# Mid485.net
KiCad netlist of a schematic drawn in Altium Designer
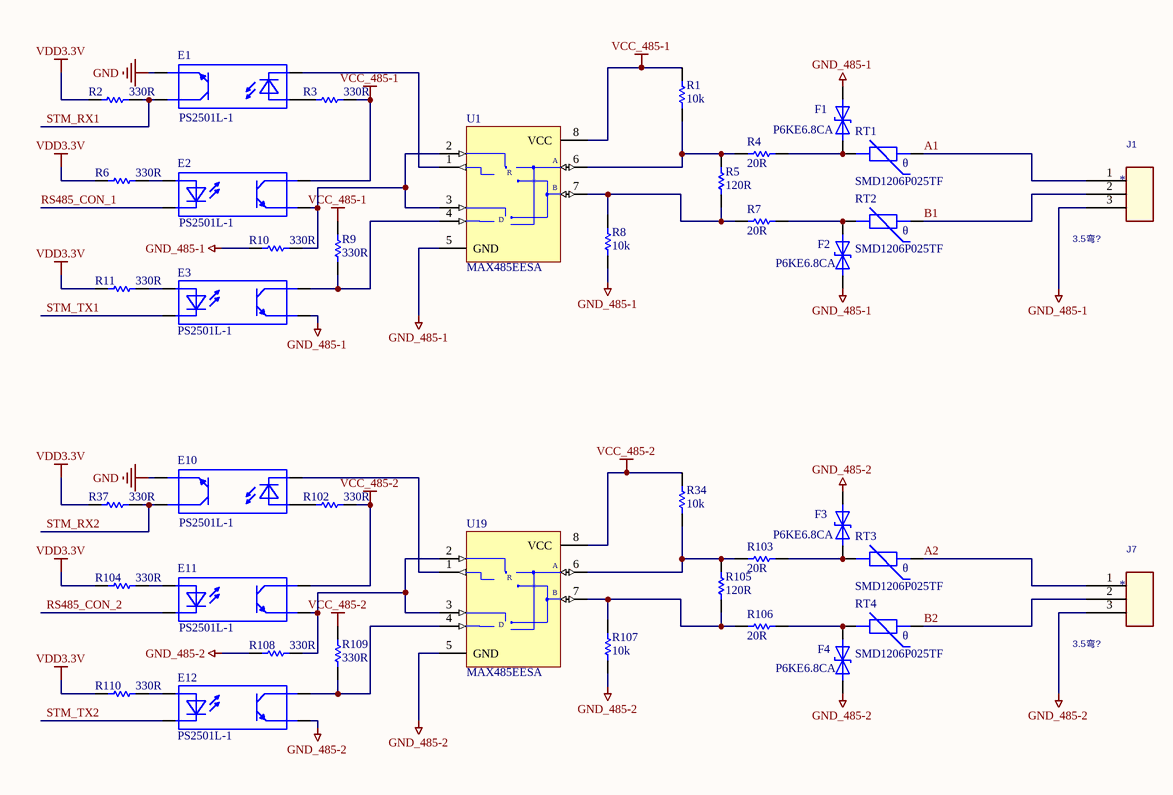
[diagram p0: Mid485.SchDoc]

(export (version "E")
  (design (tool "Eeschema 10.0.6"))
  (components
    (comp (ref "E1")
      (value "PS2501L-1")
      (footprint "NEC2501")
      (description "光耦")
      (libsource (lib "*") (part "OPTO1"))
    )
    (comp (ref "E2")
      (value "PS2501L-1")
      (footprint "NEC2501")
      (description "光耦")
      (libsource (lib "*") (part "OPTO1"))
    )
    (comp (ref "E3")
      (value "PS2501L-1")
      (footprint "NEC2501")
      (description "光耦")
      (libsource (lib "*") (part "OPTO1"))
    )
    (comp (ref "E10")
      (value "PS2501L-1")
      (footprint "NEC2501")
      (description "光耦")
      (libsource (lib "*") (part "OPTO1"))
    )
    (comp (ref "E11")
      (value "PS2501L-1")
      (footprint "NEC2501")
      (description "光耦")
      (libsource (lib "*") (part "OPTO1"))
    )
    (comp (ref "E12")
      (value "PS2501L-1")
      (footprint "NEC2501")
      (description "光耦")
      (libsource (lib "*") (part "OPTO1"))
    )
    (comp (ref "F1")
      (value "P6KE6.8CA")
      (footprint "P6KE6,8CA")
      (description "快速瞬变二极管")
      (libsource (lib "*") (part "TVS"))
    )
    (comp (ref "F2")
      (value "P6KE6.8CA")
      (footprint "P6KE6,8CA")
      (description "快速瞬变二极管")
      (libsource (lib "*") (part "TVS"))
    )
    (comp (ref "F3")
      (value "P6KE6.8CA")
      (footprint "P6KE6,8CA")
      (description "快速瞬变二极管")
      (libsource (lib "*") (part "TVS"))
    )
    (comp (ref "F4")
      (value "P6KE6.8CA")
      (footprint "P6KE6,8CA")
      (description "快速瞬变二极管")
      (libsource (lib "*") (part "TVS"))
    )
    (comp (ref "J1")
      (value "*")
      (footprint "3.5-P3")
      (fields (field (name "ALTIUM_UNNAMED_1") "3.5弯?"))
      (libsource (lib "*") (part "CON3"))
    )
    (comp (ref "J7")
      (value "*")
      (footprint "3.5-P3")
      (fields (field (name "ALTIUM_UNNAMED_1") "3.5弯?"))
      (libsource (lib "*") (part "CON3"))
    )
    (comp (ref "R1")
      (value "10k")
      (footprint "0805")
      (description "Semiconductor Resistor")
      (fields (field (name "Comment") "Res Semi") (field (name "PUBLISHER") "Altium Limited"))
      (libsource (lib "Miscellaneous Devices") (part "Res Semi"))
    )
    (comp (ref "R2")
      (value "330R")
      (footprint "0805")
      (description "Semiconductor Resistor")
      (fields (field (name "Comment") "Res Semi") (field (name "PUBLISHER") "Altium Limited"))
      (libsource (lib "Miscellaneous Devices") (part "Res Semi"))
    )
    (comp (ref "R3")
      (value "330R")
      (footprint "0805")
      (description "Semiconductor Resistor")
      (fields (field (name "Comment") "Res Semi") (field (name "PUBLISHER") "Altium Limited"))
      (libsource (lib "Miscellaneous Devices") (part "Res Semi"))
    )
    (comp (ref "R4")
      (value "20R")
      (footprint "0805")
      (description "Semiconductor Resistor")
      (fields (field (name "Comment") "Res Semi") (field (name "PUBLISHER") "Altium Limited"))
      (libsource (lib "Miscellaneous Devices") (part "Res Semi"))
    )
    (comp (ref "R5")
      (value "120R")
      (footprint "0805")
      (description "Semiconductor Resistor")
      (fields (field (name "Comment") "Res Semi") (field (name "PUBLISHER") "Altium Limited"))
      (libsource (lib "Miscellaneous Devices") (part "Res Semi"))
    )
    (comp (ref "R6")
      (value "330R")
      (footprint "0805")
      (description "Semiconductor Resistor")
      (fields (field (name "Comment") "Res Semi") (field (name "PUBLISHER") "Altium Limited"))
      (libsource (lib "Miscellaneous Devices") (part "Res Semi"))
    )
    (comp (ref "R7")
      (value "20R")
      (footprint "0805")
      (description "Semiconductor Resistor")
      (fields (field (name "Comment") "Res Semi") (field (name "PUBLISHER") "Altium Limited"))
      (libsource (lib "Miscellaneous Devices") (part "Res Semi"))
    )
    (comp (ref "R8")
      (value "10k")
      (footprint "0805")
      (description "Semiconductor Resistor")
      (fields (field (name "Comment") "Res Semi") (field (name "PUBLISHER") "Altium Limited"))
      (libsource (lib "Miscellaneous Devices") (part "Res Semi"))
    )
    (comp (ref "R9")
      (value "330R")
      (footprint "0805")
      (description "Semiconductor Resistor")
      (fields (field (name "Comment") "Res Semi") (field (name "PUBLISHER") "Altium Limited"))
      (libsource (lib "Miscellaneous Devices") (part "Res Semi"))
    )
    (comp (ref "R10")
      (value "330R")
      (footprint "0805")
      (description "Semiconductor Resistor")
      (fields (field (name "Comment") "Res Semi") (field (name "PUBLISHER") "Altium Limited"))
      (libsource (lib "Miscellaneous Devices") (part "Res Semi"))
    )
    (comp (ref "R11")
      (value "330R")
      (footprint "0805")
      (description "Semiconductor Resistor")
      (fields (field (name "Comment") "Res Semi") (field (name "PUBLISHER") "Altium Limited"))
      (libsource (lib "Miscellaneous Devices") (part "Res Semi"))
    )
    (comp (ref "R34")
      (value "10k")
      (footprint "0805")
      (description "Semiconductor Resistor")
      (fields (field (name "Comment") "Res Semi") (field (name "PUBLISHER") "Altium Limited"))
      (libsource (lib "Miscellaneous Devices") (part "Res Semi"))
    )
    (comp (ref "R37")
      (value "330R")
      (footprint "0805")
      (description "Semiconductor Resistor")
      (fields (field (name "Comment") "Res Semi") (field (name "PUBLISHER") "Altium Limited"))
      (libsource (lib "Miscellaneous Devices") (part "Res Semi"))
    )
    (comp (ref "R102")
      (value "330R")
      (footprint "0805")
      (description "Semiconductor Resistor")
      (fields (field (name "Comment") "Res Semi") (field (name "PUBLISHER") "Altium Limited"))
      (libsource (lib "Miscellaneous Devices") (part "Res Semi"))
    )
    (comp (ref "R103")
      (value "20R")
      (footprint "0805")
      (description "Semiconductor Resistor")
      (fields (field (name "Comment") "Res Semi") (field (name "PUBLISHER") "Altium Limited"))
      (libsource (lib "Miscellaneous Devices") (part "Res Semi"))
    )
    (comp (ref "R104")
      (value "330R")
      (footprint "0805")
      (description "Semiconductor Resistor")
      (fields (field (name "Comment") "Res Semi") (field (name "PUBLISHER") "Altium Limited"))
      (libsource (lib "Miscellaneous Devices") (part "Res Semi"))
    )
    (comp (ref "R105")
      (value "120R")
      (footprint "0805")
      (description "Semiconductor Resistor")
      (fields (field (name "Comment") "Res Semi") (field (name "PUBLISHER") "Altium Limited"))
      (libsource (lib "Miscellaneous Devices") (part "Res Semi"))
    )
    (comp (ref "R106")
      (value "20R")
      (footprint "0805")
      (description "Semiconductor Resistor")
      (fields (field (name "Comment") "Res Semi") (field (name "PUBLISHER") "Altium Limited"))
      (libsource (lib "Miscellaneous Devices") (part "Res Semi"))
    )
    (comp (ref "R107")
      (value "10k")
      (footprint "0805")
      (description "Semiconductor Resistor")
      (fields (field (name "Comment") "Res Semi") (field (name "PUBLISHER") "Altium Limited"))
      (libsource (lib "Miscellaneous Devices") (part "Res Semi"))
    )
    (comp (ref "R108")
      (value "330R")
      (footprint "0805")
      (description "Semiconductor Resistor")
      (fields (field (name "Comment") "Res Semi") (field (name "PUBLISHER") "Altium Limited"))
      (libsource (lib "Miscellaneous Devices") (part "Res Semi"))
    )
    (comp (ref "R109")
      (value "330R")
      (footprint "0805")
      (description "Semiconductor Resistor")
      (fields (field (name "Comment") "Res Semi") (field (name "PUBLISHER") "Altium Limited"))
      (libsource (lib "Miscellaneous Devices") (part "Res Semi"))
    )
    (comp (ref "R110")
      (value "330R")
      (footprint "0805")
      (description "Semiconductor Resistor")
      (fields (field (name "Comment") "Res Semi") (field (name "PUBLISHER") "Altium Limited"))
      (libsource (lib "Miscellaneous Devices") (part "Res Semi"))
    )
    (comp (ref "RT1")
      (value "SMD1206P025TF")
      (footprint "1206")
      (description "热敏电阻")
      (libsource (lib "*") (part "PTC"))
    )
    (comp (ref "RT2")
      (value "SMD1206P025TF")
      (footprint "1206")
      (description "热敏电阻")
      (libsource (lib "*") (part "PTC"))
    )
    (comp (ref "RT3")
      (value "SMD1206P025TF")
      (footprint "1206")
      (description "热敏电阻")
      (libsource (lib "*") (part "PTC"))
    )
    (comp (ref "RT4")
      (value "SMD1206P025TF")
      (footprint "1206")
      (description "热敏电阻")
      (libsource (lib "*") (part "PTC"))
    )
    (comp (ref "U1")
      (value "MAX485EESA")
      (footprint "NSO8")
      (description "Low-Power, Slew-Rate-Limited RS-485/RS-422 Transceiver")
      (fields (field (name "PUBLISHER") "Altium Limited"))
      (libsource (lib "main board") (part "MAX485ESA"))
    )
    (comp (ref "U19")
      (value "MAX485EESA")
      (footprint "NSO8")
      (description "Low-Power, Slew-Rate-Limited RS-485/RS-422 Transceiver")
      (fields (field (name "PUBLISHER") "Altium Limited"))
      (libsource (lib "main board") (part "MAX485ESA"))
    )
  )
  (nets
    (net (code "1") (name "/A1") (class "Default")
      (node (ref "J1") (pin "1") (pinfunction "1_1") (pintype "passive"))
      (node (ref "RT1") (pin "2") (pintype "passive"))
    )
    (net (code "2") (name "/A2") (class "Default")
      (node (ref "J7") (pin "1") (pinfunction "1_1") (pintype "passive"))
      (node (ref "RT3") (pin "2") (pintype "passive"))
    )
    (net (code "3") (name "/B1") (class "Default")
      (node (ref "J1") (pin "2") (pinfunction "2_2") (pintype "passive"))
      (node (ref "RT2") (pin "2") (pintype "passive"))
    )
    (net (code "4") (name "/B2") (class "Default")
      (node (ref "J7") (pin "2") (pinfunction "2_2") (pintype "passive"))
      (node (ref "RT4") (pin "2") (pintype "passive"))
    )
    (net (code "5") (name "/RS485_CON_1") (class "Default") (node (ref "E2") (pin "2") (pintype "passive")))
    (net (code "6") (name "/RS485_CON_2") (class "Default") (node (ref "E11") (pin "2") (pintype "passive")))
    (net (code "7") (name "/STM_RX1") (class "Default")
      (node (ref "E1") (pin "4") (pintype "passive"))
      (node (ref "R2") (pin "1") (pinfunction "1_1") (pintype "passive"))
    )
    (net (code "8") (name "/STM_RX2") (class "Default")
      (node (ref "E10") (pin "4") (pintype "passive"))
      (node (ref "R37") (pin "1") (pinfunction "1_1") (pintype "passive"))
    )
    (net (code "9") (name "/STM_TX1") (class "Default") (node (ref "E3") (pin "2") (pintype "passive")))
    (net (code "10") (name "/STM_TX2") (class "Default") (node (ref "E12") (pin "2") (pintype "passive")))
    (net (code "11") (name "GND") (class "Default")
      (node (ref "E1") (pin "3") (pintype "passive"))
      (node (ref "E10") (pin "3") (pintype "passive"))
    )
    (net (code "12") (name "GND_485-1") (class "Default")
      (node (ref "E3") (pin "3") (pintype "passive"))
      (node (ref "F1") (pin "1") (pintype "passive"))
      (node (ref "F2") (pin "2") (pintype "passive"))
      (node (ref "J1") (pin "3") (pinfunction "3_3") (pintype "passive"))
      (node (ref "R10") (pin "2") (pinfunction "2_2") (pintype "passive"))
      (node (ref "R8") (pin "2") (pinfunction "2_2") (pintype "passive"))
      (node (ref "U1") (pin "5") (pinfunction "GND_5") (pintype "power_in"))
    )
    (net (code "13") (name "GND_485-2") (class "Default")
      (node (ref "E12") (pin "3") (pintype "passive"))
      (node (ref "F3") (pin "1") (pintype "passive"))
      (node (ref "F4") (pin "2") (pintype "passive"))
      (node (ref "J7") (pin "3") (pinfunction "3_3") (pintype "passive"))
      (node (ref "R107") (pin "2") (pinfunction "2_2") (pintype "passive"))
      (node (ref "R108") (pin "2") (pinfunction "2_2") (pintype "passive"))
      (node (ref "U19") (pin "5") (pinfunction "GND_5") (pintype "power_in"))
    )
    (net (code "14") (name "Net-(E1-Pad1)") (class "Default")
      (node (ref "E1") (pin "1") (pintype "passive"))
      (node (ref "R3") (pin "2") (pinfunction "2_2") (pintype "passive"))
    )
    (net (code "15") (name "Net-(E2-Pad1)") (class "Default")
      (node (ref "E2") (pin "1") (pintype "passive"))
      (node (ref "R6") (pin "1") (pinfunction "1_1") (pintype "passive"))
    )
    (net (code "16") (name "Net-(E3-Pad1)") (class "Default")
      (node (ref "E3") (pin "1") (pintype "passive"))
      (node (ref "R11") (pin "1") (pinfunction "1_1") (pintype "passive"))
    )
    (net (code "17") (name "Net-(E10-Pad1)") (class "Default")
      (node (ref "E10") (pin "1") (pintype "passive"))
      (node (ref "R102") (pin "2") (pinfunction "2_2") (pintype "passive"))
    )
    (net (code "18") (name "Net-(E11-Pad1)") (class "Default")
      (node (ref "E11") (pin "1") (pintype "passive"))
      (node (ref "R104") (pin "1") (pinfunction "1_1") (pintype "passive"))
    )
    (net (code "19") (name "Net-(E12-Pad1)") (class "Default")
      (node (ref "E12") (pin "1") (pintype "passive"))
      (node (ref "R110") (pin "1") (pinfunction "1_1") (pintype "passive"))
    )
    (net (code "20") (name "Net-(F1-Pad2)") (class "Default")
      (node (ref "F1") (pin "2") (pintype "passive"))
      (node (ref "R4") (pin "2") (pinfunction "2_2") (pintype "passive"))
      (node (ref "RT1") (pin "1") (pintype "passive"))
    )
    (net (code "21") (name "Net-(F2-Pad1)") (class "Default")
      (node (ref "F2") (pin "1") (pintype "passive"))
      (node (ref "R7") (pin "2") (pinfunction "2_2") (pintype "passive"))
      (node (ref "RT2") (pin "1") (pintype "passive"))
    )
    (net (code "22") (name "Net-(F3-Pad2)") (class "Default")
      (node (ref "F3") (pin "2") (pintype "passive"))
      (node (ref "R103") (pin "2") (pinfunction "2_2") (pintype "passive"))
      (node (ref "RT3") (pin "1") (pintype "passive"))
    )
    (net (code "23") (name "Net-(F4-Pad1)") (class "Default")
      (node (ref "F4") (pin "1") (pintype "passive"))
      (node (ref "R106") (pin "2") (pinfunction "2_2") (pintype "passive"))
      (node (ref "RT4") (pin "1") (pintype "passive"))
    )
    (net (code "24") (name "Net-(U1-A)") (class "Default")
      (node (ref "R1") (pin "2") (pinfunction "2_2") (pintype "passive"))
      (node (ref "R4") (pin "1") (pinfunction "1_1") (pintype "passive"))
      (node (ref "R5") (pin "1") (pinfunction "1_1") (pintype "passive"))
      (node (ref "U1") (pin "6") (pinfunction "A_6") (pintype "bidirectional"))
    )
    (net (code "25") (name "Net-(U1-B)") (class "Default")
      (node (ref "R5") (pin "2") (pinfunction "2_2") (pintype "passive"))
      (node (ref "R7") (pin "1") (pinfunction "1_1") (pintype "passive"))
      (node (ref "R8") (pin "1") (pinfunction "1_1") (pintype "passive"))
      (node (ref "U1") (pin "7") (pinfunction "B_7") (pintype "bidirectional"))
    )
    (net (code "26") (name "Net-(U1-DE)") (class "Default")
      (node (ref "E2") (pin "3") (pintype "passive"))
      (node (ref "R10") (pin "1") (pinfunction "1_1") (pintype "passive"))
      (node (ref "U1") (pin "2") (pinfunction "~{RE}_2") (pintype "input"))
      (node (ref "U1") (pin "3") (pinfunction "DE_3") (pintype "input"))
    )
    (net (code "27") (name "Net-(U1-DI)") (class "Default")
      (node (ref "E3") (pin "4") (pintype "passive"))
      (node (ref "R9") (pin "2") (pinfunction "2_2") (pintype "passive"))
      (node (ref "U1") (pin "4") (pinfunction "DI_4") (pintype "input"))
    )
    (net (code "28") (name "Net-(U1-RO)") (class "Default")
      (node (ref "E1") (pin "2") (pintype "passive"))
      (node (ref "U1") (pin "1") (pinfunction "RO_1") (pintype "output"))
    )
    (net (code "29") (name "Net-(U19-A)") (class "Default")
      (node (ref "R103") (pin "1") (pinfunction "1_1") (pintype "passive"))
      (node (ref "R105") (pin "1") (pinfunction "1_1") (pintype "passive"))
      (node (ref "R34") (pin "2") (pinfunction "2_2") (pintype "passive"))
      (node (ref "U19") (pin "6") (pinfunction "A_6") (pintype "bidirectional"))
    )
    (net (code "30") (name "Net-(U19-B)") (class "Default")
      (node (ref "R105") (pin "2") (pinfunction "2_2") (pintype "passive"))
      (node (ref "R106") (pin "1") (pinfunction "1_1") (pintype "passive"))
      (node (ref "R107") (pin "1") (pinfunction "1_1") (pintype "passive"))
      (node (ref "U19") (pin "7") (pinfunction "B_7") (pintype "bidirectional"))
    )
    (net (code "31") (name "Net-(U19-DE)") (class "Default")
      (node (ref "E11") (pin "3") (pintype "passive"))
      (node (ref "R108") (pin "1") (pinfunction "1_1") (pintype "passive"))
      (node (ref "U19") (pin "2") (pinfunction "~{RE}_2") (pintype "input"))
      (node (ref "U19") (pin "3") (pinfunction "DE_3") (pintype "input"))
    )
    (net (code "32") (name "Net-(U19-DI)") (class "Default")
      (node (ref "E12") (pin "4") (pintype "passive"))
      (node (ref "R109") (pin "2") (pinfunction "2_2") (pintype "passive"))
      (node (ref "U19") (pin "4") (pinfunction "DI_4") (pintype "input"))
    )
    (net (code "33") (name "Net-(U19-RO)") (class "Default")
      (node (ref "E10") (pin "2") (pintype "passive"))
      (node (ref "U19") (pin "1") (pinfunction "RO_1") (pintype "output"))
    )
    (net (code "34") (name "VCC_485-1") (class "Default")
      (node (ref "E2") (pin "4") (pintype "passive"))
      (node (ref "R1") (pin "1") (pinfunction "1_1") (pintype "passive"))
      (node (ref "R3") (pin "1") (pinfunction "1_1") (pintype "passive"))
      (node (ref "R9") (pin "1") (pinfunction "1_1") (pintype "passive"))
      (node (ref "U1") (pin "8") (pinfunction "VCC_8") (pintype "power_in"))
    )
    (net (code "35") (name "VCC_485-2") (class "Default")
      (node (ref "E11") (pin "4") (pintype "passive"))
      (node (ref "R102") (pin "1") (pinfunction "1_1") (pintype "passive"))
      (node (ref "R109") (pin "1") (pinfunction "1_1") (pintype "passive"))
      (node (ref "R34") (pin "1") (pinfunction "1_1") (pintype "passive"))
      (node (ref "U19") (pin "8") (pinfunction "VCC_8") (pintype "power_in"))
    )
    (net (code "36") (name "VDD3.3V") (class "Default")
      (node (ref "R104") (pin "2") (pinfunction "2_2") (pintype "passive"))
      (node (ref "R11") (pin "2") (pinfunction "2_2") (pintype "passive"))
      (node (ref "R110") (pin "2") (pinfunction "2_2") (pintype "passive"))
      (node (ref "R2") (pin "2") (pinfunction "2_2") (pintype "passive"))
      (node (ref "R37") (pin "2") (pinfunction "2_2") (pintype "passive"))
      (node (ref "R6") (pin "2") (pinfunction "2_2") (pintype "passive"))
    )
  )
)
